# Encoders.net
KiCad netlist of a schematic drawn in Altium Designer
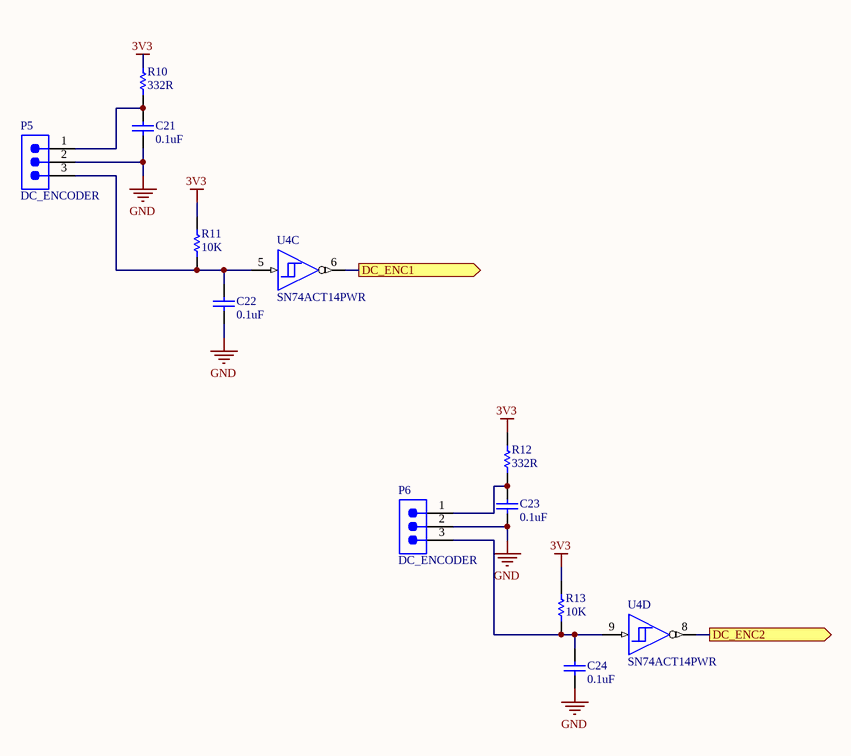
[diagram p0: Encoders.SchDoc]

(export (version "E")
  (design (tool "Eeschema 10.0.6"))
  (components
    (comp (ref "C21")
      (value "0.1uF")
      (footprint "CAPC1608X90X35LL15T15")
      (description "Chip Capacitor, 100 nF, +/- 10%, 50 V, -55 to 125 degC, 0603 (1608 Metric), RoHS, Tape and Reel")
      (fields (field (name "TOLERANCE") "10%"))
      (libsource (lib "Altium Content Vault") (part "CAP-NP-2"))
    )
    (comp (ref "C22")
      (value "0.1uF")
      (footprint "CAPC1608X90X35LL15T15")
      (description "Chip Capacitor, 100 nF, +/- 10%, 50 V, -55 to 125 degC, 0603 (1608 Metric), RoHS, Tape and Reel")
      (fields (field (name "TOLERANCE") "10%"))
      (libsource (lib "Altium Content Vault") (part "CAP-NP-2"))
    )
    (comp (ref "C23")
      (value "0.1uF")
      (footprint "CAPC1608X90X35LL15T15")
      (description "Chip Capacitor, 100 nF, +/- 10%, 50 V, -55 to 125 degC, 0603 (1608 Metric), RoHS, Tape and Reel")
      (fields (field (name "TOLERANCE") "10%"))
      (libsource (lib "Altium Content Vault") (part "CAP-NP-2"))
    )
    (comp (ref "C24")
      (value "0.1uF")
      (footprint "CAPC1608X90X35LL15T15")
      (description "Chip Capacitor, 100 nF, +/- 10%, 50 V, -55 to 125 degC, 0603 (1608 Metric), RoHS, Tape and Reel")
      (fields (field (name "TOLERANCE") "10%"))
      (libsource (lib "Altium Content Vault") (part "CAP-NP-2"))
    )
    (comp (ref "P5")
      (value "DC_ENCODER")
      (footprint "SMTC-TSW-103-07-X-S")
      (description "0.025\" SQ Post Header, Through-hole, Vertical, -55 to 125 degC, 2.54 mm Pitch, 3-Pin, Male, RoHS")
      (fields (field (name "MANUFACTURER") "Samtec") (field (name "PARTNUMBER") "TSW-103-07-L-S"))
      (libsource (lib "Altium Content Vault") (part "SMTC-TSW-103-X-X-S-X"))
    )
    (comp (ref "P6")
      (value "DC_ENCODER")
      (footprint "SMTC-TSW-103-07-X-S")
      (description "0.025\" SQ Post Header, Through-hole, Vertical, -55 to 125 degC, 2.54 mm Pitch, 3-Pin, Male, RoHS")
      (fields (field (name "MANUFACTURER") "Samtec") (field (name "PARTNUMBER") "TSW-103-07-L-S"))
      (libsource (lib "Altium Content Vault") (part "SMTC-TSW-103-X-X-S-X"))
    )
    (comp (ref "R10")
      (value "332R")
      (footprint "RESC1608X55X30ML15T15")
      (fields (field (name "PART NUMBER") "ERJ-3EKF3320V") (field (name "MANUFACTURER") "Panasonic"))
      (libsource (lib "Altium Content Vault") (part "RES"))
    )
    (comp (ref "R11")
      (value "10K")
      (footprint "RESC1609X50X30ML10T20")
      (fields (field (name "MANUFACTURER") "Vishay Dale") (field (name "PART NUMBER") "CRCW060310K0JNEA"))
      (libsource (lib "Altium Content Vault") (part "RES"))
    )
    (comp (ref "R12")
      (value "332R")
      (footprint "RESC1608X55X30ML15T15")
      (fields (field (name "PART NUMBER") "ERJ-3EKF3320V") (field (name "MANUFACTURER") "Panasonic"))
      (libsource (lib "Altium Content Vault") (part "RES"))
    )
    (comp (ref "R13")
      (value "10K")
      (footprint "RESC1609X50X30ML10T20")
      (fields (field (name "MANUFACTURER") "Vishay Dale") (field (name "PART NUMBER") "CRCW060310K0JNEA"))
      (libsource (lib "Altium Content Vault") (part "RES"))
    )
    (comp (ref "U4")
      (value "SN74ACT14PWR")
      (footprint "PW0014A_N")
      (description "Hex Schmitt-Trigger Inverters, PW0014A, LARGE T&R")
      (fields
        (field (name "GENERIC PART NUMBER") "SN74ACT14")
        (field (name "MANUFACTURER") "Texas Instruments")
      )
      (libsource (lib "Altium Content Vault") (part "TI-CD_SNX4XXXXXX4X_19A-14-SCHMITT"))
    )
  )
  (nets
    (net (code "1") (name "/DC_ENC1") (class "Default")
      (node (ref "U4") (pin "6") (pinfunction "~{3Y}_6") (pintype "output"))
    )
    (net (code "2") (name "/DC_ENC2") (class "Default")
      (node (ref "U4") (pin "8") (pinfunction "~{4Y}_8") (pintype "output"))
    )
    (net (code "3") (name "3V3") (class "Default")
      (node (ref "R10") (pin "2") (pinfunction "2_2") (pintype "passive"))
      (node (ref "R11") (pin "1") (pinfunction "1_1") (pintype "passive"))
      (node (ref "R12") (pin "2") (pinfunction "2_2") (pintype "passive"))
      (node (ref "R13") (pin "1") (pinfunction "1_1") (pintype "passive"))
    )
    (net (code "4") (name "GND") (class "Default")
      (node (ref "C21") (pin "1") (pinfunction "1_1") (pintype "passive"))
      (node (ref "C22") (pin "1") (pinfunction "1_1") (pintype "passive"))
      (node (ref "C23") (pin "1") (pinfunction "1_1") (pintype "passive"))
      (node (ref "C24") (pin "1") (pinfunction "1_1") (pintype "passive"))
      (node (ref "P5") (pin "2") (pinfunction "Ground_2") (pintype "passive"))
      (node (ref "P6") (pin "2") (pinfunction "Ground_2") (pintype "passive"))
    )
    (net (code "5") (name "Net-(P5-5V)") (class "Default")
      (node (ref "C21") (pin "2") (pinfunction "2_2") (pintype "passive"))
      (node (ref "P5") (pin "1") (pinfunction "5V_1") (pintype "passive"))
      (node (ref "R10") (pin "1") (pinfunction "1_1") (pintype "passive"))
    )
    (net (code "6") (name "Net-(P5-Signal)") (class "Default")
      (node (ref "C22") (pin "2") (pinfunction "2_2") (pintype "passive"))
      (node (ref "P5") (pin "3") (pinfunction "Signal_3") (pintype "passive"))
      (node (ref "R11") (pin "2") (pinfunction "2_2") (pintype "passive"))
      (node (ref "U4") (pin "5") (pinfunction "3A_5") (pintype "input"))
    )
    (net (code "7") (name "Net-(P6-5V)") (class "Default")
      (node (ref "C23") (pin "2") (pinfunction "2_2") (pintype "passive"))
      (node (ref "P6") (pin "1") (pinfunction "5V_1") (pintype "passive"))
      (node (ref "R12") (pin "1") (pinfunction "1_1") (pintype "passive"))
    )
    (net (code "8") (name "Net-(P6-Signal)") (class "Default")
      (node (ref "C24") (pin "2") (pinfunction "2_2") (pintype "passive"))
      (node (ref "P6") (pin "3") (pinfunction "Signal_3") (pintype "passive"))
      (node (ref "R13") (pin "2") (pinfunction "2_2") (pintype "passive"))
      (node (ref "U4") (pin "9") (pinfunction "4A_9") (pintype "input"))
    )
  )
)
